# button_input.net
KiCad netlist of a schematic drawn in Altium Designer
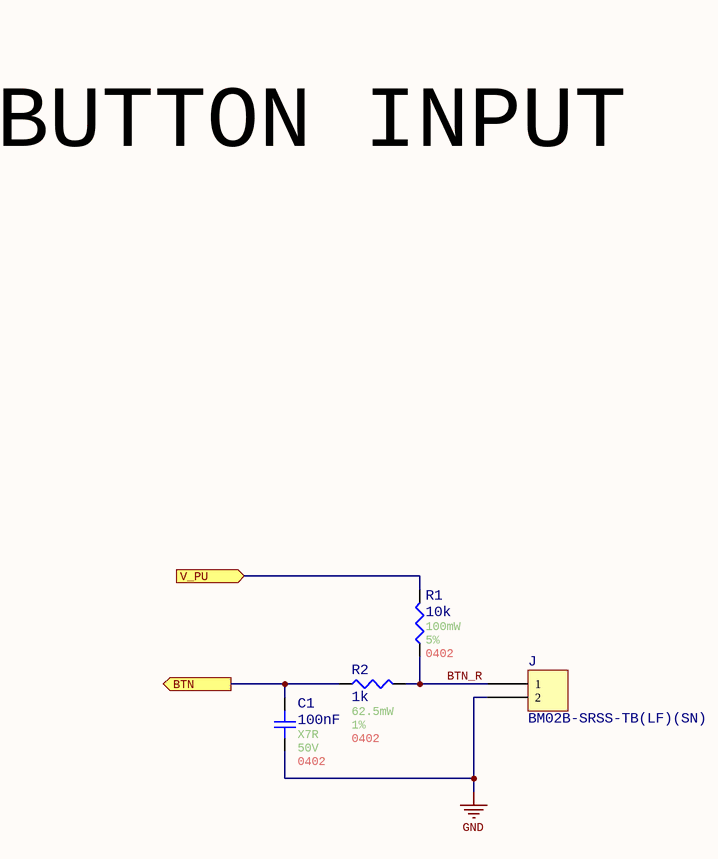
[diagram p0: button_input.SchDoc]

(export (version "E")
  (design (tool "Eeschema 10.0.6"))
  (components
    (comp (ref "C1")
      (value "100nF")
      (footprint "Generic 0402 capacitor")
      (fields
        (field (name "TEMPERATURE COEFFICIENT") "X7R")
        (field (name "VOLTAGE RATING") "50V")
        (field (name "CASE/PACKAGE") "0402")
        (field (name "TOLERANCE") "10%")
        (field (name "Comment") "GRT155R71H104KE01D")
      )
      (libsource (lib "Raise Robotics") (part "Unpolarized Capacitor"))
    )
    (comp (ref "J")
      (value "BM02B-SRSS-TB(LF)(SN)")
      (footprint "JST BM02B-SRSS-TB")
      (description "CONN HEADER SMD 2POS 1MM")
      (fields (field (name "MANUFACTURER") "JST Sales America Inc."))
      (libsource (lib "Celestial Altium Library - altium_library") (part "2 Pin"))
    )
    (comp (ref "R1")
      (value "10k")
      (footprint "Generic 0402 Resistor")
      (description "Res Thick Film 0402 10K Ohm 5% 1/10W ±200ppm/°C Molded SMD Punched Carrier T/R")
      (fields
        (field (name "POWER") "100mW")
        (field (name "TOLERANCE") "5%")
        (field (name "CASE/PACKAGE") "0402")
        (field (name "Comment") "ERJ-2GEJ103X")
      )
      (libsource (lib "Raise Robotics") (part "Resistor"))
    )
    (comp (ref "R2")
      (value "1k")
      (footprint "Generic 0402 Resistor")
      (fields
        (field (name "POWER") "62.5mW")
        (field (name "TOLERANCE") "1%")
        (field (name "CASE/PACKAGE") "0402")
        (field (name "MANUFACTURER PART NUMBER") "Blank")
        (field (name "Comment") "WR04X1001FTL")
      )
      (libsource (lib "Raise Robotics") (part "Resistor"))
    )
  )
  (nets
    (net (code "1") (name "/BTN") (class "Default")
      (node (ref "C1") (pin "2") (pinfunction "2_2") (pintype "passive"))
      (node (ref "R2") (pin "1") (pinfunction "1_1") (pintype "passive"))
    )
    (net (code "2") (name "/BTN_R") (class "Default")
      (node (ref "J") (pin "1") (pinfunction "1_1") (pintype "passive"))
      (node (ref "R1") (pin "1") (pinfunction "1_1") (pintype "passive"))
      (node (ref "R2") (pin "2") (pinfunction "2_2") (pintype "passive"))
    )
    (net (code "3") (name "/V_PU") (class "Default")
      (node (ref "R1") (pin "2") (pinfunction "2_2") (pintype "passive"))
    )
    (net (code "4") (name "GND") (class "Default")
      (node (ref "C1") (pin "1") (pinfunction "1_1") (pintype "passive"))
      (node (ref "J") (pin "2") (pinfunction "2_2") (pintype "passive"))
    )
  )
)
